# side_panel_V5.net
KiCad netlist of a schematic drawn in EAGLE
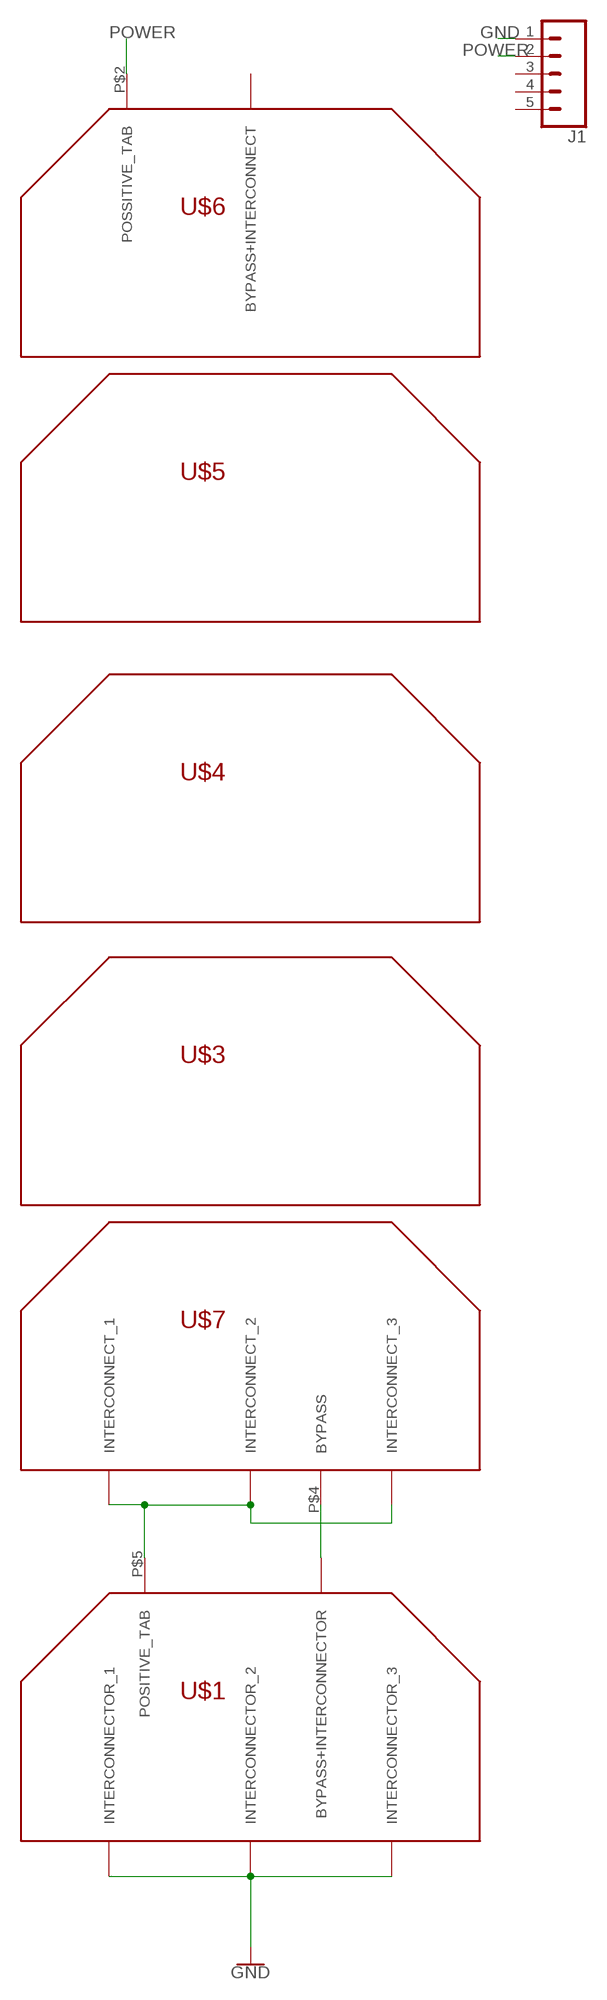
[diagram p0: schematic, sheet 1]

(export (version "E")
  (design (tool "Eeschema 10.0.6"))
  (components
    (comp (ref "J1")
      (value "CONN_05LOCK")
      (footprint "eagle-import:1X05_LOCK")
      (libsource (lib "eagle-import") (part "CONN_05LOCK"))
    )
    (comp (ref "U$1")
      (value "SOLAR_CELL_STAND-ALONE")
      (footprint "eagle-import:SOLAR_CELL_STAND-ALONE")
      (libsource (lib "eagle-import") (part "SOLAR_CELL_STAND-ALONE"))
    )
    (comp (ref "U$3")
      (value "SOALAR_CELL_OUTLINE")
      (footprint "eagle-import:SOLAR_CELL_OUTLINE")
      (libsource (lib "eagle-import") (part "SOALAR_CELL_OUTLINE"))
    )
    (comp (ref "U$4")
      (value "SOALAR_CELL_OUTLINE")
      (footprint "eagle-import:SOLAR_CELL_OUTLINE")
      (libsource (lib "eagle-import") (part "SOALAR_CELL_OUTLINE"))
    )
    (comp (ref "U$5")
      (value "SOALAR_CELL_OUTLINE")
      (footprint "eagle-import:SOLAR_CELL_OUTLINE")
      (libsource (lib "eagle-import") (part "SOALAR_CELL_OUTLINE"))
    )
    (comp (ref "U$6")
      (value "SOLAR_CELL_TOP")
      (footprint "eagle-import:SOLAR_CELL_TOP_SHORT-PAD")
      (libsource (lib "eagle-import") (part "SOLAR_CELL_TOP"))
    )
    (comp (ref "U$7")
      (value "SOLAR_CELL_BOTTOM+BYPASS")
      (footprint "eagle-import:SOLAR_CELL_BOTTOM+BYPASS")
      (libsource (lib "eagle-import") (part "SOLAR_CELL_BOTTOM+BYPASS"))
    )
  )
  (nets
    (net (code "1") (name "/POWER") (class "Default")
      (node (ref "J1") (pin "2") (pinfunction "2_2") (pintype "passive"))
      (node (ref "U$6") (pin "P$2") (pinfunction "POSSITIVE_TAB_P$2") (pintype "bidirectional"))
    )
    (net (code "2") (name "GND") (class "Default")
      (node (ref "J1") (pin "1") (pinfunction "1_1") (pintype "passive"))
      (node (ref "U$1") (pin "P$1") (pinfunction "INTERCONNECTOR_1_P$1") (pintype "bidirectional"))
      (node (ref "U$1") (pin "P$2") (pinfunction "INTERCONNECTOR_2_P$2") (pintype "bidirectional"))
      (node (ref "U$1") (pin "P$3") (pinfunction "INTERCONNECTOR_3_P$3") (pintype "bidirectional"))
    )
    (net (code "3") (name "Net-(U$1-BYPASS+INTERCONNECTOR)") (class "Default")
      (node (ref "U$1") (pin "P$4") (pinfunction "BYPASS+INTERCONNECTOR_P$4") (pintype "bidirectional"))
      (node (ref "U$7") (pin "P$4") (pinfunction "BYPASS_P$4") (pintype "bidirectional"))
    )
    (net (code "4") (name "Net-(U$1-POSITIVE_TAB)") (class "Default")
      (node (ref "U$1") (pin "P$5") (pinfunction "POSITIVE_TAB_P$5") (pintype "bidirectional"))
      (node (ref "U$7") (pin "P$1") (pinfunction "INTERCONNECT_1_P$1") (pintype "bidirectional"))
      (node (ref "U$7") (pin "P$2") (pinfunction "INTERCONNECT_2_P$2") (pintype "bidirectional"))
      (node (ref "U$7") (pin "P$3") (pinfunction "INTERCONNECT_3_P$3") (pintype "bidirectional"))
    )
    (net (code "5") (name "unconnected-(J1-Pad3)") (class "Default")
      (node (ref "J1") (pin "3") (pinfunction "3_3") (pintype "passive"))
    )
    (net (code "6") (name "unconnected-(J1-Pad4)") (class "Default")
      (node (ref "J1") (pin "4") (pinfunction "4_4") (pintype "passive"))
    )
    (net (code "7") (name "unconnected-(J1-Pad5)") (class "Default")
      (node (ref "J1") (pin "5") (pinfunction "5_5") (pintype "passive"))
    )
    (net (code "8") (name "unconnected-(U$6-BYPASS+INTERCONNECT-PadP$1)") (class "Default")
      (node (ref "U$6") (pin "P$1") (pinfunction "BYPASS+INTERCONNECT_P$1") (pintype "bidirectional"))
    )
  )
)
